# SMPS.net
KiCad netlist of a schematic drawn in EAGLE
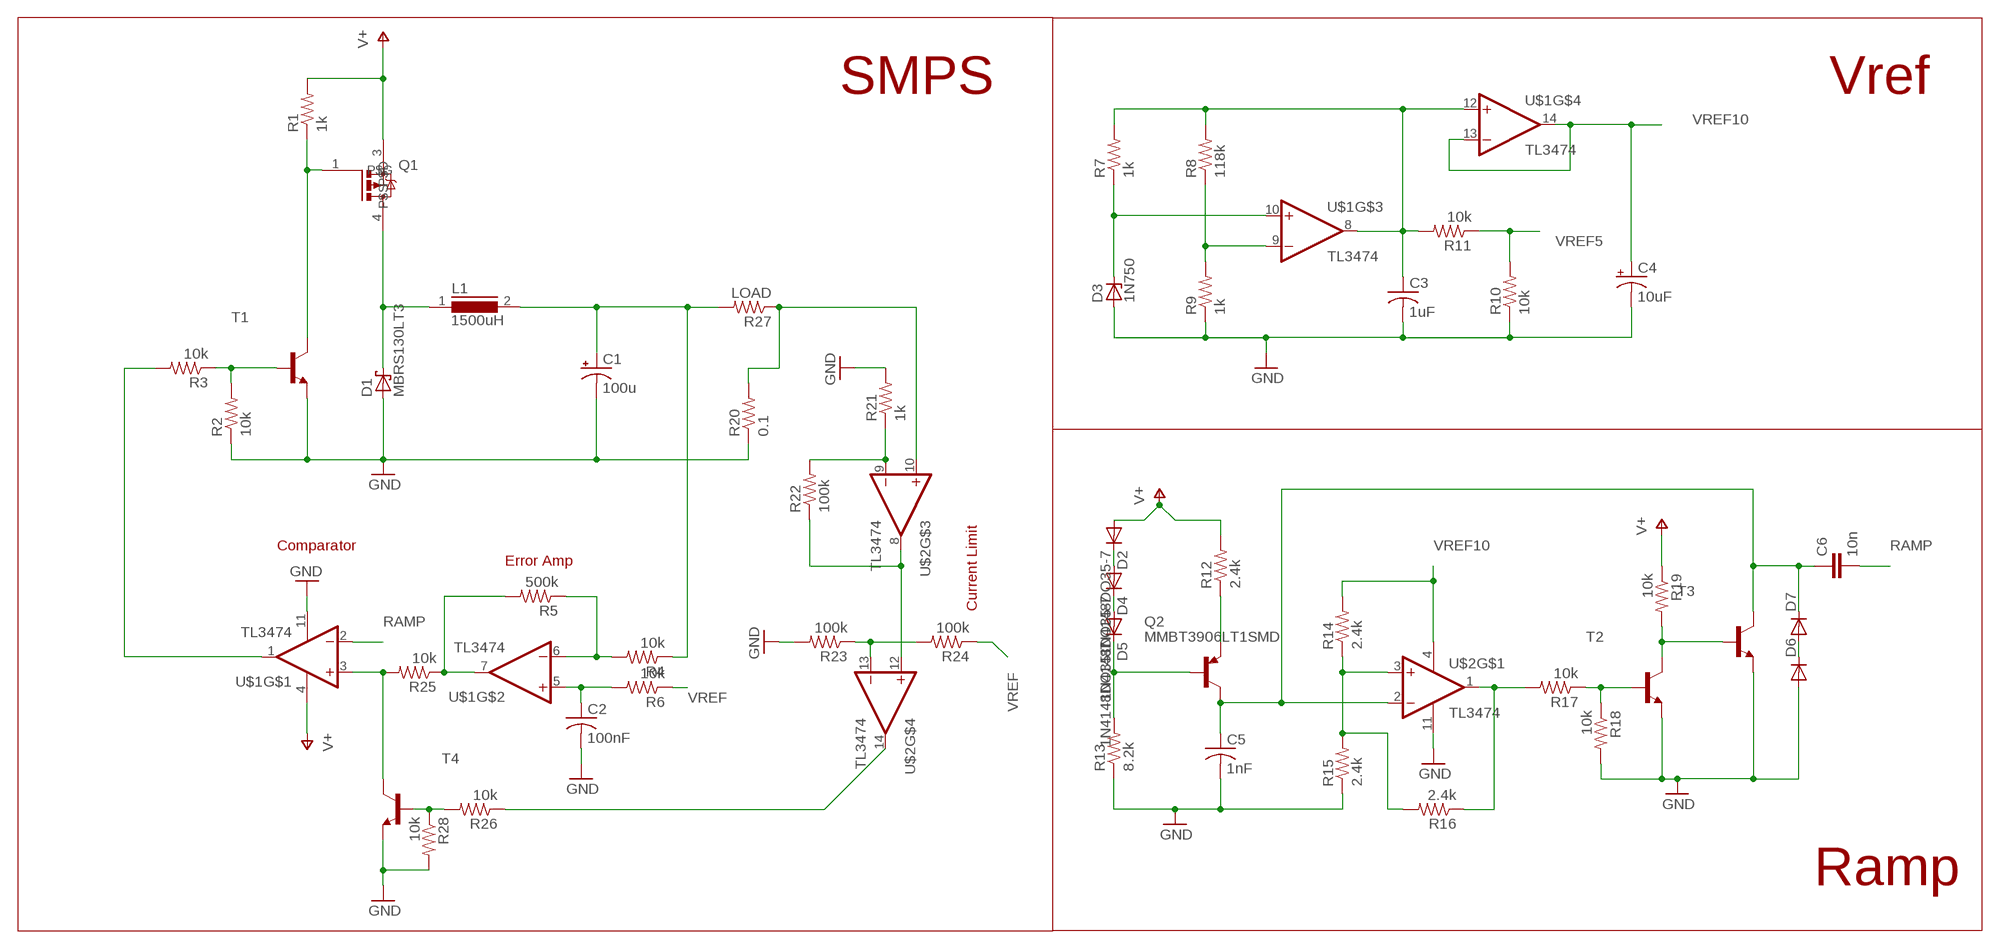
[diagram p0: schematic, sheet 1]

(export (version "E")
  (design (tool "Eeschema 10.0.6"))
  (components
    (comp (ref "C1")
      (value "100u")
      (footprint "eagle-import:E7,5-16")
      (libsource (lib "eagle-import") (part "CPOL-USE7.5-16"))
    )
    (comp (ref "C2")
      (value "100nF")
      (footprint "eagle-import:C0805")
      (libsource (lib "eagle-import") (part "C-USC0805"))
    )
    (comp (ref "C3")
      (value "1uF")
      (footprint "eagle-import:C0805")
      (libsource (lib "eagle-import") (part "C-USC0805"))
    )
    (comp (ref "C4")
      (value "10uF")
      (footprint "eagle-import:E7,5-16")
      (libsource (lib "eagle-import") (part "CPOL-USE7.5-16"))
    )
    (comp (ref "C5")
      (value "1nF")
      (footprint "eagle-import:C0805")
      (libsource (lib "eagle-import") (part "C-USC0805"))
    )
    (comp (ref "C6")
      (value "10n")
      (footprint "eagle-import:C0805")
      (libsource (lib "eagle-import") (part "C-EUC0805"))
    )
    (comp (ref "D1")
      (value "MBRS130LT3")
      (footprint "eagle-import:SMB")
      (libsource (lib "eagle-import") (part "MBRS130LT3"))
    )
    (comp (ref "D2")
      (value "1N4148DO35-7")
      (footprint "eagle-import:DO35-7")
      (libsource (lib "eagle-import") (part "1N4148DO35-7"))
    )
    (comp (ref "D3")
      (value "1N750")
      (footprint "eagle-import:ZDIO-7.5")
      (libsource (lib "eagle-import") (part "ZENER-DIODEZD-7.5"))
    )
    (comp (ref "D4")
      (value "1N4148DO35-7")
      (footprint "eagle-import:DO35-7")
      (libsource (lib "eagle-import") (part "1N4148DO35-7"))
    )
    (comp (ref "D5")
      (value "1N4148DO35-7")
      (footprint "eagle-import:DO35-7")
      (libsource (lib "eagle-import") (part "1N4148DO35-7"))
    )
    (comp (ref "D6")
      (value "1N4148DO35-7")
      (footprint "eagle-import:DO35-7")
      (libsource (lib "eagle-import") (part "1N4148DO35-7"))
    )
    (comp (ref "D7")
      (value "1N4148DO35-7")
      (footprint "eagle-import:DO35-7")
      (libsource (lib "eagle-import") (part "1N4148DO35-7"))
    )
    (comp (ref "L1")
      (value "1500uH")
      (footprint "eagle-import:82114R")
      (libsource (lib "eagle-import") (part "82114R"))
    )
    (comp (ref "Q1")
      (value "IRFR9024NDPAK")
      (footprint "eagle-import:D-PAK_TO252AA")
      (libsource (lib "eagle-import") (part "IRFR9024NDPAK"))
    )
    (comp (ref "Q2")
      (value "MMBT3906LT1SMD")
      (footprint "eagle-import:SOT23-BEC")
      (libsource (lib "eagle-import") (part "MMBT3906SMDLT1"))
    )
    (comp (ref "R1")
      (value "1k")
      (footprint "eagle-import:R0805")
      (libsource (lib "eagle-import") (part "R-US_R0805"))
    )
    (comp (ref "R2")
      (value "10k")
      (footprint "eagle-import:R0805")
      (libsource (lib "eagle-import") (part "R-US_R0805"))
    )
    (comp (ref "R3")
      (value "10k")
      (footprint "eagle-import:R0805")
      (libsource (lib "eagle-import") (part "R-US_R0805"))
    )
    (comp (ref "R4")
      (value "10k")
      (footprint "eagle-import:R0805")
      (libsource (lib "eagle-import") (part "R-US_R0805"))
    )
    (comp (ref "R5")
      (value "500k")
      (footprint "eagle-import:R0805")
      (libsource (lib "eagle-import") (part "R-US_R0805"))
    )
    (comp (ref "R6")
      (value "10k")
      (footprint "eagle-import:R0805")
      (libsource (lib "eagle-import") (part "R-US_R0805"))
    )
    (comp (ref "R7")
      (value "1k")
      (footprint "eagle-import:R0805")
      (libsource (lib "eagle-import") (part "R-US_R0805"))
    )
    (comp (ref "R8")
      (value "118k")
      (footprint "eagle-import:R0805")
      (libsource (lib "eagle-import") (part "R-US_R0805"))
    )
    (comp (ref "R9")
      (value "1k")
      (footprint "eagle-import:R0805")
      (libsource (lib "eagle-import") (part "R-US_R0805"))
    )
    (comp (ref "R10")
      (value "10k")
      (footprint "eagle-import:R0805")
      (libsource (lib "eagle-import") (part "R-US_R0805"))
    )
    (comp (ref "R11")
      (value "10k")
      (footprint "eagle-import:R0805")
      (libsource (lib "eagle-import") (part "R-US_R0805"))
    )
    (comp (ref "R12")
      (value "2.4k")
      (footprint "eagle-import:R0805")
      (libsource (lib "eagle-import") (part "R-US_R0805"))
    )
    (comp (ref "R13")
      (value "8.2k")
      (footprint "eagle-import:R0805")
      (libsource (lib "eagle-import") (part "R-US_R0805"))
    )
    (comp (ref "R14")
      (value "2.4k")
      (footprint "eagle-import:R0805")
      (libsource (lib "eagle-import") (part "R-US_R0805"))
    )
    (comp (ref "R15")
      (value "2.4k")
      (footprint "eagle-import:R0805")
      (libsource (lib "eagle-import") (part "R-US_R0805"))
    )
    (comp (ref "R16")
      (value "2.4k")
      (footprint "eagle-import:R0805")
      (libsource (lib "eagle-import") (part "R-US_R0805"))
    )
    (comp (ref "R17")
      (value "10k")
      (footprint "eagle-import:R0805")
      (libsource (lib "eagle-import") (part "R-US_R0805"))
    )
    (comp (ref "R18")
      (value "10k")
      (footprint "eagle-import:R0805")
      (libsource (lib "eagle-import") (part "R-US_R0805"))
    )
    (comp (ref "R19")
      (value "10k")
      (footprint "eagle-import:R0805")
      (libsource (lib "eagle-import") (part "R-US_R0805"))
    )
    (comp (ref "R20")
      (value "0.1")
      (footprint "eagle-import:R1206")
      (libsource (lib "eagle-import") (part "R-US_R1206"))
    )
    (comp (ref "R21")
      (value "1k")
      (footprint "eagle-import:R0805")
      (libsource (lib "eagle-import") (part "R-US_R0805"))
    )
    (comp (ref "R22")
      (value "100k")
      (footprint "eagle-import:R0805")
      (libsource (lib "eagle-import") (part "R-US_R0805"))
    )
    (comp (ref "R23")
      (value "100k")
      (footprint "eagle-import:R0805")
      (libsource (lib "eagle-import") (part "R-US_R0805"))
    )
    (comp (ref "R24")
      (value "100k")
      (footprint "eagle-import:R0805")
      (libsource (lib "eagle-import") (part "R-US_R0805"))
    )
    (comp (ref "R25")
      (value "10k")
      (footprint "eagle-import:R0805")
      (libsource (lib "eagle-import") (part "R-US_R0805"))
    )
    (comp (ref "R26")
      (value "10k")
      (footprint "eagle-import:R0805")
      (libsource (lib "eagle-import") (part "R-US_R0805"))
    )
    (comp (ref "R27")
      (value "LOAD")
      (footprint "eagle-import:R0805")
      (libsource (lib "eagle-import") (part "R-US_R0805"))
    )
    (comp (ref "R28")
      (value "10k")
      (footprint "eagle-import:R0805")
      (libsource (lib "eagle-import") (part "R-US_R0805"))
    )
    (comp (ref "T1")
      (value "MMBT2222ALT1-NPN-SOT23-BEC")
      (footprint "eagle-import:SOT23-BEC")
      (libsource (lib "eagle-import") (part "-NPN-SOT23-BECMMBT2222ALT1"))
    )
    (comp (ref "T2")
      (value "MMBT2222ALT1-NPN-SOT23-BEC")
      (footprint "eagle-import:SOT23-BEC")
      (libsource (lib "eagle-import") (part "-NPN-SOT23-BECMMBT2222ALT1"))
    )
    (comp (ref "T3")
      (value "MMBT2222ALT1-NPN-SOT23-BEC")
      (footprint "eagle-import:SOT23-BEC")
      (libsource (lib "eagle-import") (part "-NPN-SOT23-BECMMBT2222ALT1"))
    )
    (comp (ref "T4")
      (value "MMBT2222ALT1-NPN-SOT23-BEC")
      (footprint "eagle-import:SOT23-BEC")
      (libsource (lib "eagle-import") (part "-NPN-SOT23-BECMMBT2222ALT1"))
    )
    (comp (ref "U$1")
      (value "TL3474")
      (footprint "eagle-import:SO14")
      (libsource (lib "eagle-import") (part "TL3474"))
    )
    (comp (ref "U$2")
      (value "TL3474")
      (footprint "eagle-import:SO14")
      (libsource (lib "eagle-import") (part "TL3474"))
    )
  )
  (nets
    (net (code "1") (name "/RAMP") (class "Default")
      (node (ref "C6") (pin "2") (pinfunction "2_2") (pintype "passive"))
      (node (ref "U$1") (pin "2") (pinfunction "-IN_2") (pintype "input"))
    )
    (net (code "2") (name "/VREF") (class "Default")
      (node (ref "R24") (pin "1") (pinfunction "1_1") (pintype "passive"))
      (node (ref "R6") (pin "1") (pinfunction "1_1") (pintype "passive"))
    )
    (net (code "3") (name "/VREF5") (class "Default")
      (node (ref "R10") (pin "2") (pinfunction "2_2") (pintype "passive"))
      (node (ref "R11") (pin "1") (pinfunction "1_1") (pintype "passive"))
    )
    (net (code "4") (name "/VREF10") (class "Default")
      (node (ref "C4") (pin "+") (pinfunction "+_+") (pintype "passive"))
      (node (ref "R14") (pin "2") (pinfunction "2_2") (pintype "passive"))
      (node (ref "U$1") (pin "13") (pinfunction "-IN_13") (pintype "input"))
      (node (ref "U$1") (pin "14") (pinfunction "OUT_14") (pintype "output"))
      (node (ref "U$2") (pin "4") (pinfunction "V+_4") (pintype "power_in"))
    )
    (net (code "5") (name "GND") (class "Default")
      (node (ref "C1") (pin "-") (pinfunction "-_-") (pintype "passive"))
      (node (ref "C2") (pin "2") (pinfunction "2_2") (pintype "passive"))
      (node (ref "C3") (pin "2") (pinfunction "2_2") (pintype "passive"))
      (node (ref "C4") (pin "-") (pinfunction "-_-") (pintype "passive"))
      (node (ref "C5") (pin "2") (pinfunction "2_2") (pintype "passive"))
      (node (ref "D1") (pin "A") (pinfunction "A_A") (pintype "passive"))
      (node (ref "D3") (pin "A") (pinfunction "A_A") (pintype "passive"))
      (node (ref "D6") (pin "A") (pinfunction "A_A") (pintype "passive"))
      (node (ref "R10") (pin "1") (pinfunction "1_1") (pintype "passive"))
      (node (ref "R13") (pin "1") (pinfunction "1_1") (pintype "passive"))
      (node (ref "R15") (pin "1") (pinfunction "1_1") (pintype "passive"))
      (node (ref "R18") (pin "2") (pinfunction "2_2") (pintype "passive"))
      (node (ref "R2") (pin "1") (pinfunction "1_1") (pintype "passive"))
      (node (ref "R20") (pin "1") (pinfunction "1_1") (pintype "passive"))
      (node (ref "R21") (pin "2") (pinfunction "2_2") (pintype "passive"))
      (node (ref "R23") (pin "2") (pinfunction "2_2") (pintype "passive"))
      (node (ref "R28") (pin "2") (pinfunction "2_2") (pintype "passive"))
      (node (ref "R9") (pin "1") (pinfunction "1_1") (pintype "passive"))
      (node (ref "T1") (pin "E") (pinfunction "E_E") (pintype "passive"))
      (node (ref "T2") (pin "E") (pinfunction "E_E") (pintype "passive"))
      (node (ref "T3") (pin "E") (pinfunction "E_E") (pintype "passive"))
      (node (ref "T4") (pin "E") (pinfunction "E_E") (pintype "passive"))
      (node (ref "U$1") (pin "11") (pinfunction "V-_11") (pintype "power_in"))
      (node (ref "U$2") (pin "11") (pinfunction "V-_11") (pintype "power_in"))
    )
    (net (code "6") (name "Net-(C1-Pad+)") (class "Default")
      (node (ref "C1") (pin "+") (pinfunction "+_+") (pintype "passive"))
      (node (ref "L1") (pin "2") (pinfunction "2_2") (pintype "passive"))
      (node (ref "R27") (pin "2") (pinfunction "2_2") (pintype "passive"))
      (node (ref "R4") (pin "1") (pinfunction "1_1") (pintype "passive"))
    )
    (net (code "7") (name "Net-(D2-PadC)") (class "Default")
      (node (ref "D2") (pin "C") (pinfunction "C_C") (pintype "passive"))
      (node (ref "D4") (pin "A") (pinfunction "A_A") (pintype "passive"))
    )
    (net (code "8") (name "Net-(D4-PadC)") (class "Default")
      (node (ref "D4") (pin "C") (pinfunction "C_C") (pintype "passive"))
      (node (ref "D5") (pin "A") (pinfunction "A_A") (pintype "passive"))
    )
    (net (code "9") (name "Net-(D5-PadC)") (class "Default")
      (node (ref "D5") (pin "C") (pinfunction "C_C") (pintype "passive"))
      (node (ref "Q2") (pin "B") (pinfunction "B_B") (pintype "passive"))
      (node (ref "R13") (pin "2") (pinfunction "2_2") (pintype "passive"))
    )
    (net (code "10") (name "Net-(D6-PadC)") (class "Default")
      (node (ref "D6") (pin "C") (pinfunction "C_C") (pintype "passive"))
      (node (ref "D7") (pin "A") (pinfunction "A_A") (pintype "passive"))
    )
    (net (code "11") (name "Net-(Q1-P$D)") (class "Default")
      (node (ref "D1") (pin "C") (pinfunction "C_C") (pintype "passive"))
      (node (ref "L1") (pin "1") (pinfunction "1_1") (pintype "passive"))
      (node (ref "Q1") (pin "4") (pinfunction "P$D_4") (pintype "bidirectional"))
    )
    (net (code "12") (name "Net-(Q1-P$G)") (class "Default")
      (node (ref "Q1") (pin "1") (pinfunction "P$G_1") (pintype "bidirectional"))
      (node (ref "R1") (pin "1") (pinfunction "1_1") (pintype "passive"))
      (node (ref "T1") (pin "C") (pinfunction "C_C") (pintype "passive"))
    )
    (net (code "13") (name "Net-(Q2-PadE)") (class "Default")
      (node (ref "Q2") (pin "E") (pinfunction "E_E") (pintype "passive"))
      (node (ref "R12") (pin "1") (pinfunction "1_1") (pintype "passive"))
    )
    (net (code "14") (name "Net-(R2-Pad2)") (class "Default")
      (node (ref "R2") (pin "2") (pinfunction "2_2") (pintype "passive"))
      (node (ref "R3") (pin "1") (pinfunction "1_1") (pintype "passive"))
      (node (ref "T1") (pin "B") (pinfunction "B_B") (pintype "passive"))
    )
    (net (code "15") (name "Net-(R17-Pad1)") (class "Default")
      (node (ref "R17") (pin "1") (pinfunction "1_1") (pintype "passive"))
      (node (ref "R18") (pin "1") (pinfunction "1_1") (pintype "passive"))
      (node (ref "T2") (pin "B") (pinfunction "B_B") (pintype "passive"))
    )
    (net (code "16") (name "Net-(R19-Pad2)") (class "Default")
      (node (ref "R19") (pin "2") (pinfunction "2_2") (pintype "passive"))
      (node (ref "T2") (pin "C") (pinfunction "C_C") (pintype "passive"))
      (node (ref "T3") (pin "B") (pinfunction "B_B") (pintype "passive"))
    )
    (net (code "17") (name "Net-(R26-Pad2)") (class "Default")
      (node (ref "R26") (pin "2") (pinfunction "2_2") (pintype "passive"))
      (node (ref "R28") (pin "1") (pinfunction "1_1") (pintype "passive"))
      (node (ref "T4") (pin "B") (pinfunction "B_B") (pintype "passive"))
    )
    (net (code "18") (name "Net-(U$1A-+IN)") (class "Default")
      (node (ref "R25") (pin "2") (pinfunction "2_2") (pintype "passive"))
      (node (ref "T4") (pin "C") (pinfunction "C_C") (pintype "passive"))
      (node (ref "U$1") (pin "3") (pinfunction "+IN_3") (pintype "input"))
    )
    (net (code "19") (name "Net-(U$1A-OUT)") (class "Default")
      (node (ref "R3") (pin "2") (pinfunction "2_2") (pintype "passive"))
      (node (ref "U$1") (pin "1") (pinfunction "OUT_1") (pintype "output"))
    )
    (net (code "20") (name "Net-(U$1B-+IN)") (class "Default")
      (node (ref "C2") (pin "1") (pinfunction "1_1") (pintype "passive"))
      (node (ref "R6") (pin "2") (pinfunction "2_2") (pintype "passive"))
      (node (ref "U$1") (pin "5") (pinfunction "+IN_5") (pintype "input"))
    )
    (net (code "21") (name "Net-(U$1B--IN)") (class "Default")
      (node (ref "R4") (pin "2") (pinfunction "2_2") (pintype "passive"))
      (node (ref "R5") (pin "1") (pinfunction "1_1") (pintype "passive"))
      (node (ref "U$1") (pin "6") (pinfunction "-IN_6") (pintype "input"))
    )
    (net (code "22") (name "Net-(U$1B-OUT)") (class "Default")
      (node (ref "R25") (pin "1") (pinfunction "1_1") (pintype "passive"))
      (node (ref "R5") (pin "2") (pinfunction "2_2") (pintype "passive"))
      (node (ref "U$1") (pin "7") (pinfunction "OUT_7") (pintype "output"))
    )
    (net (code "23") (name "Net-(U$1C-+IN)") (class "Default")
      (node (ref "D3") (pin "C") (pinfunction "C_C") (pintype "passive"))
      (node (ref "R7") (pin "1") (pinfunction "1_1") (pintype "passive"))
      (node (ref "U$1") (pin "10") (pinfunction "+IN_10") (pintype "input"))
    )
    (net (code "24") (name "Net-(U$1C--IN)") (class "Default")
      (node (ref "R8") (pin "1") (pinfunction "1_1") (pintype "passive"))
      (node (ref "R9") (pin "2") (pinfunction "2_2") (pintype "passive"))
      (node (ref "U$1") (pin "9") (pinfunction "-IN_9") (pintype "input"))
    )
    (net (code "25") (name "Net-(U$1C-OUT)") (class "Default")
      (node (ref "C3") (pin "1") (pinfunction "1_1") (pintype "passive"))
      (node (ref "R11") (pin "2") (pinfunction "2_2") (pintype "passive"))
      (node (ref "R7") (pin "2") (pinfunction "2_2") (pintype "passive"))
      (node (ref "R8") (pin "2") (pinfunction "2_2") (pintype "passive"))
      (node (ref "U$1") (pin "12") (pinfunction "+IN_12") (pintype "input"))
      (node (ref "U$1") (pin "8") (pinfunction "OUT_8") (pintype "output"))
    )
    (net (code "26") (name "Net-(U$2A-+IN)") (class "Default")
      (node (ref "R14") (pin "1") (pinfunction "1_1") (pintype "passive"))
      (node (ref "R15") (pin "2") (pinfunction "2_2") (pintype "passive"))
      (node (ref "R16") (pin "2") (pinfunction "2_2") (pintype "passive"))
      (node (ref "U$2") (pin "3") (pinfunction "+IN_3") (pintype "input"))
    )
    (net (code "27") (name "Net-(U$2A--IN)") (class "Default")
      (node (ref "C5") (pin "1") (pinfunction "1_1") (pintype "passive"))
      (node (ref "C6") (pin "1") (pinfunction "1_1") (pintype "passive"))
      (node (ref "D7") (pin "C") (pinfunction "C_C") (pintype "passive"))
      (node (ref "Q2") (pin "C") (pinfunction "C_C") (pintype "passive"))
      (node (ref "T3") (pin "C") (pinfunction "C_C") (pintype "passive"))
      (node (ref "U$2") (pin "2") (pinfunction "-IN_2") (pintype "input"))
    )
    (net (code "28") (name "Net-(U$2A-OUT)") (class "Default")
      (node (ref "R16") (pin "1") (pinfunction "1_1") (pintype "passive"))
      (node (ref "R17") (pin "2") (pinfunction "2_2") (pintype "passive"))
      (node (ref "U$2") (pin "1") (pinfunction "OUT_1") (pintype "output"))
    )
    (net (code "29") (name "Net-(U$2C-+IN)") (class "Default")
      (node (ref "R20") (pin "2") (pinfunction "2_2") (pintype "passive"))
      (node (ref "R27") (pin "1") (pinfunction "1_1") (pintype "passive"))
      (node (ref "U$2") (pin "10") (pinfunction "+IN_10") (pintype "input"))
    )
    (net (code "30") (name "Net-(U$2C--IN)") (class "Default")
      (node (ref "R21") (pin "1") (pinfunction "1_1") (pintype "passive"))
      (node (ref "R22") (pin "2") (pinfunction "2_2") (pintype "passive"))
      (node (ref "U$2") (pin "9") (pinfunction "-IN_9") (pintype "input"))
    )
    (net (code "31") (name "Net-(U$2C-OUT)") (class "Default")
      (node (ref "R22") (pin "1") (pinfunction "1_1") (pintype "passive"))
      (node (ref "U$2") (pin "12") (pinfunction "+IN_12") (pintype "input"))
      (node (ref "U$2") (pin "8") (pinfunction "OUT_8") (pintype "output"))
    )
    (net (code "32") (name "Net-(U$2D--IN)") (class "Default")
      (node (ref "R23") (pin "1") (pinfunction "1_1") (pintype "passive"))
      (node (ref "R24") (pin "2") (pinfunction "2_2") (pintype "passive"))
      (node (ref "U$2") (pin "13") (pinfunction "-IN_13") (pintype "input"))
    )
    (net (code "33") (name "Net-(U$2D-OUT)") (class "Default")
      (node (ref "R26") (pin "1") (pinfunction "1_1") (pintype "passive"))
      (node (ref "U$2") (pin "14") (pinfunction "OUT_14") (pintype "output"))
    )
    (net (code "34") (name "V+") (class "Default")
      (node (ref "D2") (pin "A") (pinfunction "A_A") (pintype "passive"))
      (node (ref "Q1") (pin "3") (pinfunction "P$S_3") (pintype "bidirectional"))
      (node (ref "R1") (pin "2") (pinfunction "2_2") (pintype "passive"))
      (node (ref "R12") (pin "2") (pinfunction "2_2") (pintype "passive"))
      (node (ref "R19") (pin "1") (pinfunction "1_1") (pintype "passive"))
      (node (ref "U$1") (pin "4") (pinfunction "V+_4") (pintype "power_in"))
    )
  )
)
